# pc_afe4490_brk_v2.net
KiCad netlist of a schematic drawn in EAGLE
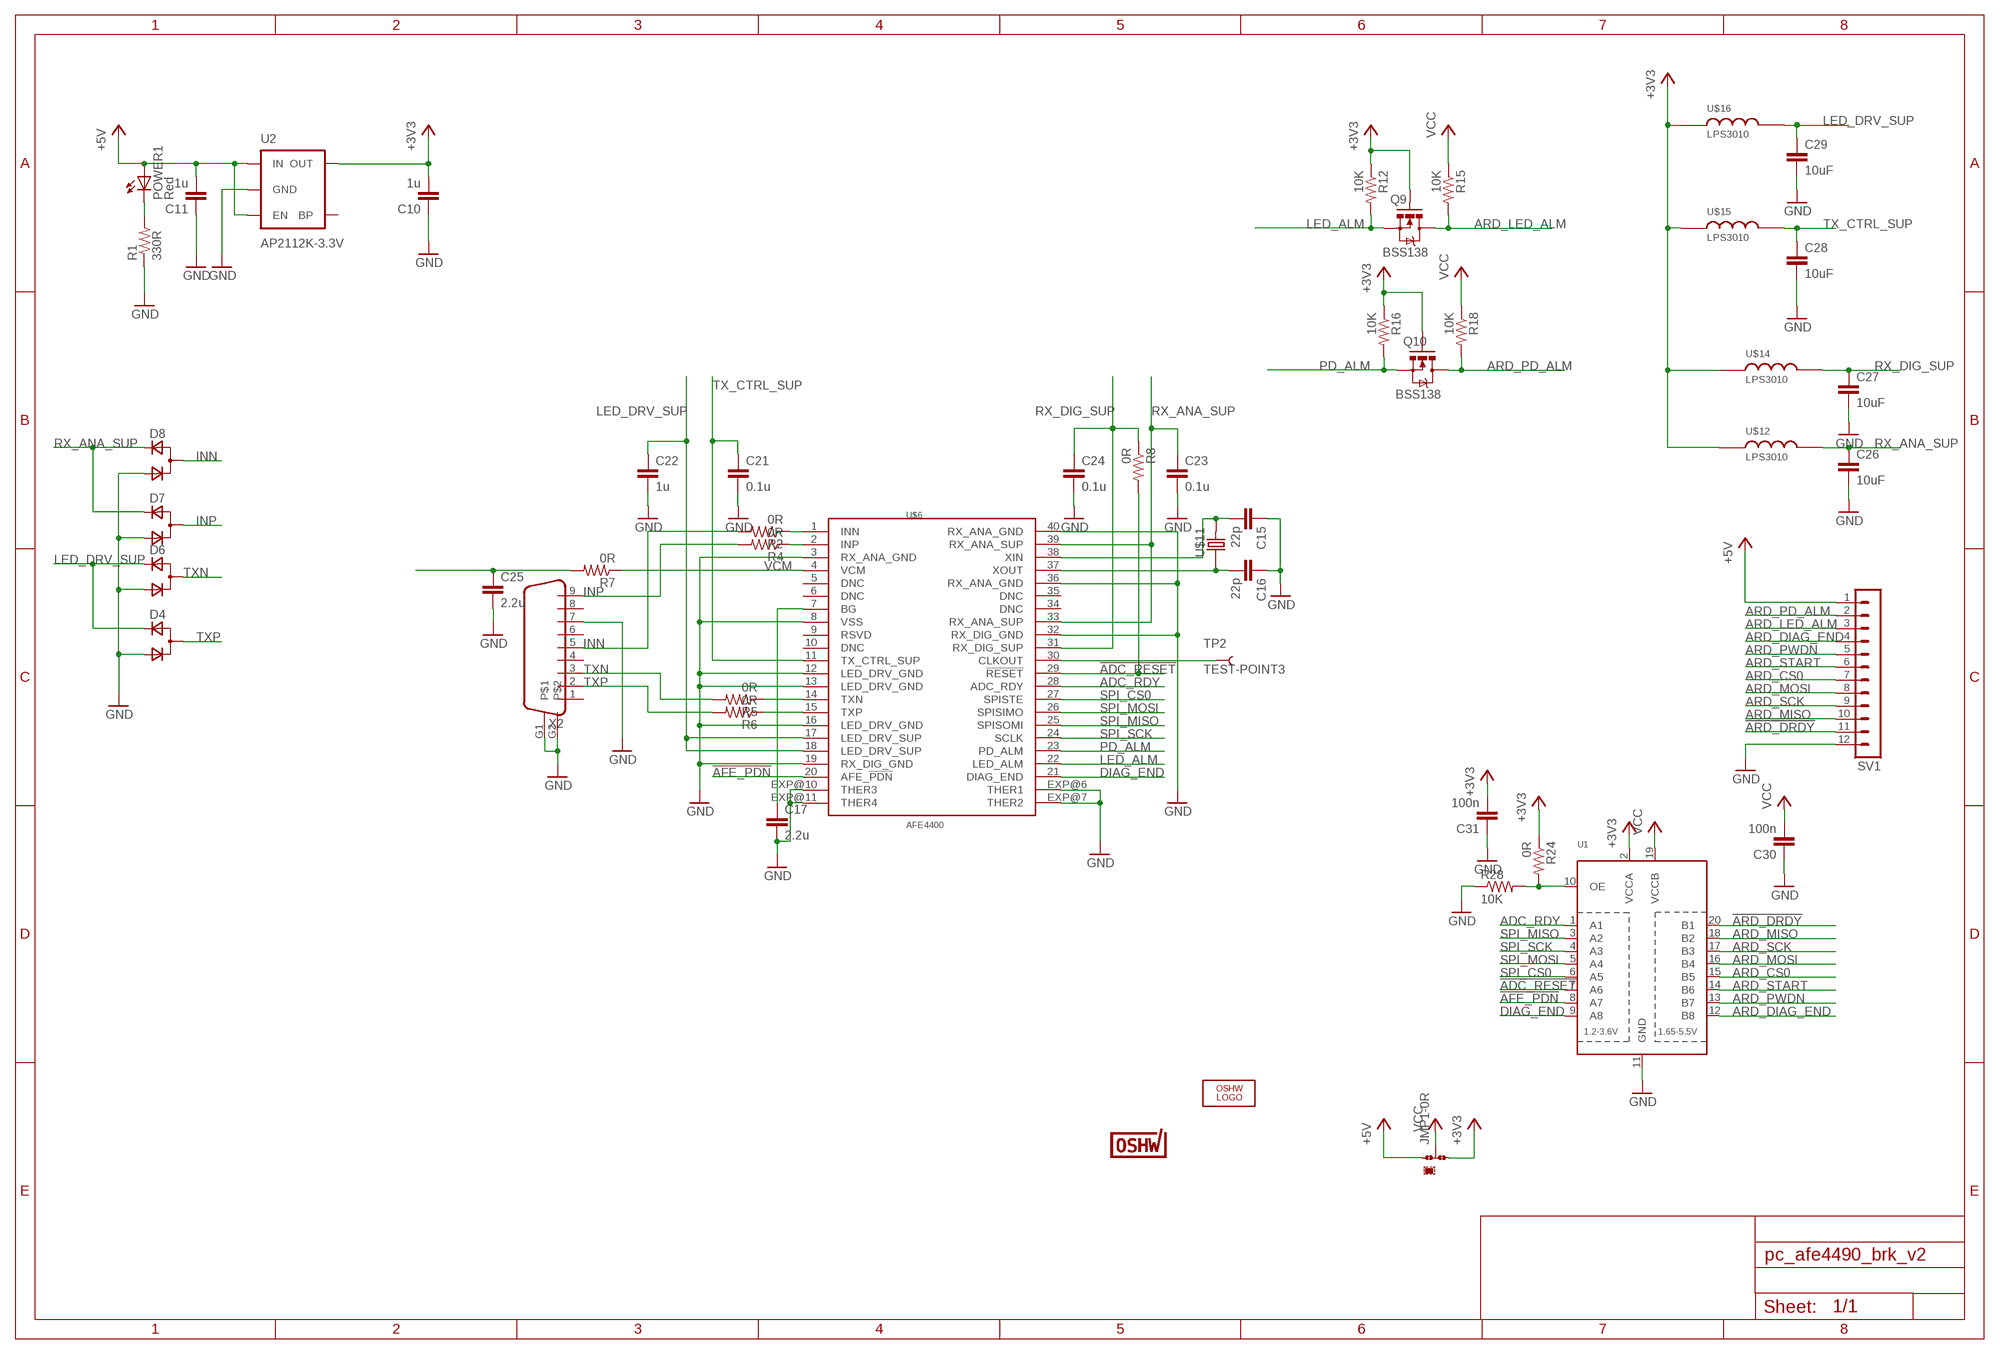
[diagram p0: schematic, sheet 1]

(export (version "E")
  (design (tool "Eeschema 10.0.6"))
  (components
    (comp (ref "C10")
      (value "1u")
      (footprint "eagle-import:C0805")
      (libsource (lib "eagle-import") (part "C-EUC0805"))
    )
    (comp (ref "C11")
      (value "1u")
      (footprint "eagle-import:C0805")
      (libsource (lib "eagle-import") (part "C-EUC0805"))
    )
    (comp (ref "C15")
      (value "22p")
      (footprint "eagle-import:C0402")
      (libsource (lib "eagle-import") (part "C-EUC0402"))
    )
    (comp (ref "C16")
      (value "22p")
      (footprint "eagle-import:C0402")
      (libsource (lib "eagle-import") (part "C-EUC0402"))
    )
    (comp (ref "C17")
      (value "2.2u")
      (footprint "eagle-import:C0402")
      (libsource (lib "eagle-import") (part "C-EUC0402"))
    )
    (comp (ref "C21")
      (value "0.1u")
      (footprint "eagle-import:C0805")
      (libsource (lib "eagle-import") (part "C-EUC0805"))
    )
    (comp (ref "C22")
      (value "1u")
      (footprint "eagle-import:C0805")
      (libsource (lib "eagle-import") (part "C-EUC0805"))
    )
    (comp (ref "C23")
      (value "0.1u")
      (footprint "eagle-import:C0805")
      (libsource (lib "eagle-import") (part "C-EUC0805"))
    )
    (comp (ref "C24")
      (value "0.1u")
      (footprint "eagle-import:C0805")
      (libsource (lib "eagle-import") (part "C-EUC0805"))
    )
    (comp (ref "C25")
      (value "2.2u")
      (footprint "eagle-import:C0402")
      (libsource (lib "eagle-import") (part "C-EUC0402"))
    )
    (comp (ref "C26")
      (value "10uF")
      (footprint "eagle-import:C0805")
      (libsource (lib "eagle-import") (part "C-EUC0805"))
    )
    (comp (ref "C27")
      (value "10uF")
      (footprint "eagle-import:C0805")
      (libsource (lib "eagle-import") (part "C-EUC0805"))
    )
    (comp (ref "C28")
      (value "10uF")
      (footprint "eagle-import:C0805")
      (libsource (lib "eagle-import") (part "C-EUC0805"))
    )
    (comp (ref "C29")
      (value "10uF")
      (footprint "eagle-import:C0805")
      (libsource (lib "eagle-import") (part "C-EUC0805"))
    )
    (comp (ref "C30")
      (value "100n")
      (footprint "eagle-import:C0402")
      (libsource (lib "eagle-import") (part "C-EUC0402"))
    )
    (comp (ref "C31")
      (value "100n")
      (footprint "eagle-import:C0402")
      (libsource (lib "eagle-import") (part "C-EUC0402"))
    )
    (comp (ref "D4")
      (value "D_ACACSOT323")
      (footprint "eagle-import:SOT323")
      (libsource (lib "eagle-import") (part "D_ACACSOT323"))
    )
    (comp (ref "D6")
      (value "D_ACACSOT323")
      (footprint "eagle-import:SOT323")
      (libsource (lib "eagle-import") (part "D_ACACSOT323"))
    )
    (comp (ref "D7")
      (value "D_ACACSOT323")
      (footprint "eagle-import:SOT323")
      (libsource (lib "eagle-import") (part "D_ACACSOT323"))
    )
    (comp (ref "D8")
      (value "D_ACACSOT323")
      (footprint "eagle-import:SOT323")
      (libsource (lib "eagle-import") (part "D_ACACSOT323"))
    )
    (comp (ref "JMP1")
      (value "0R-JUMPA")
      (footprint "eagle-import:A0R-JMP")
      (libsource (lib "eagle-import") (part "0R-JUMPA"))
    )
    (comp (ref "LOGO2")
      (value "OSHW_LOGO_FILLX0200-NT")
      (footprint "eagle-import:OSHW_FILLX200_NOTEXT")
      (libsource (lib "eagle-import") (part "OSHW_LOGO_FILLX0200-NT"))
    )
    (comp (ref "POWER1")
      (value "Red")
      (footprint "eagle-import:CHIPLED_0603")
      (libsource (lib "eagle-import") (part "LEDCHIPLED_0603"))
    )
    (comp (ref "Q9")
      (value "BSS138")
      (footprint "eagle-import:SOT23-3")
      (libsource (lib "eagle-import") (part "MOSFET-NCHANNELSMD"))
    )
    (comp (ref "Q10")
      (value "BSS138")
      (footprint "eagle-import:SOT23-3")
      (libsource (lib "eagle-import") (part "MOSFET-NCHANNELSMD"))
    )
    (comp (ref "R1")
      (value "330R")
      (footprint "eagle-import:R0805")
      (libsource (lib "eagle-import") (part "R-US_R0805"))
    )
    (comp (ref "R2")
      (value "0R")
      (footprint "eagle-import:R0402")
      (libsource (lib "eagle-import") (part "R-US_R0402"))
    )
    (comp (ref "R4")
      (value "0R")
      (footprint "eagle-import:R0402")
      (libsource (lib "eagle-import") (part "R-US_R0402"))
    )
    (comp (ref "R5")
      (value "0R")
      (footprint "eagle-import:R0805")
      (libsource (lib "eagle-import") (part "R-US_R0805"))
    )
    (comp (ref "R6")
      (value "0R")
      (footprint "eagle-import:R0805")
      (libsource (lib "eagle-import") (part "R-US_R0805"))
    )
    (comp (ref "R7")
      (value "0R")
      (footprint "eagle-import:R0402")
      (libsource (lib "eagle-import") (part "R-US_R0402"))
    )
    (comp (ref "R8")
      (value "0R")
      (footprint "eagle-import:R0805")
      (libsource (lib "eagle-import") (part "R-US_R0805"))
    )
    (comp (ref "R12")
      (value "10K")
      (footprint "eagle-import:0805")
      (libsource (lib "eagle-import") (part "RESISTOR0805-RES"))
    )
    (comp (ref "R15")
      (value "10K")
      (footprint "eagle-import:0805")
      (libsource (lib "eagle-import") (part "RESISTOR0805-RES"))
    )
    (comp (ref "R16")
      (value "10K")
      (footprint "eagle-import:0805")
      (libsource (lib "eagle-import") (part "RESISTOR0805-RES"))
    )
    (comp (ref "R18")
      (value "10K")
      (footprint "eagle-import:0805")
      (libsource (lib "eagle-import") (part "RESISTOR0805-RES"))
    )
    (comp (ref "R24")
      (value "0R")
      (footprint "eagle-import:0805")
      (libsource (lib "eagle-import") (part "RESISTOR0805-RES"))
    )
    (comp (ref "R28")
      (value "10K")
      (footprint "eagle-import:0805")
      (libsource (lib "eagle-import") (part "RESISTOR0805-RES"))
    )
    (comp (ref "SV1")
      (value "MA12-1")
      (footprint "eagle-import:MA12-1")
      (libsource (lib "eagle-import") (part "MA12-1"))
    )
    (comp (ref "TP2")
      (value "TEST-POINT3")
      (footprint "eagle-import:PAD.03X.03")
      (libsource (lib "eagle-import") (part "TEST-POINT3"))
    )
    (comp (ref "U$1")
      (value "PROTY-LOGO")
      (footprint "eagle-import:LOGO-PROTY")
      (libsource (lib "eagle-import") (part "PROTY-LOGO"))
    )
    (comp (ref "U$3")
      (value "PROTY_LOGO_WITH_TEXT")
      (footprint "eagle-import:PROTY_WITH_TEXT")
      (libsource (lib "eagle-import") (part "PROTY_LOGO_WITH_TEXT"))
    )
    (comp (ref "U$4")
      (value "CERT-SMALL")
      (footprint "eagle-import:CERT-SMALL-SILK")
      (libsource (lib "eagle-import") (part "CERT-SMALL"))
    )
    (comp (ref "U$6")
      (value "AFE4400")
      (footprint "eagle-import:QFN-40")
      (libsource (lib "eagle-import") (part "AFE4400"))
    )
    (comp (ref "U$11")
      (value "ABM3")
      (footprint "eagle-import:ABM3")
      (libsource (lib "eagle-import") (part "ABM3"))
    )
    (comp (ref "U$12")
      (value "LPS3010")
      (footprint "eagle-import:LPS")
      (libsource (lib "eagle-import") (part "LPS"))
    )
    (comp (ref "U$14")
      (value "LPS3010")
      (footprint "eagle-import:LPS")
      (libsource (lib "eagle-import") (part "LPS"))
    )
    (comp (ref "U$15")
      (value "LPS3010")
      (footprint "eagle-import:LPS")
      (libsource (lib "eagle-import") (part "LPS"))
    )
    (comp (ref "U$16")
      (value "LPS3010")
      (footprint "eagle-import:LPS")
      (libsource (lib "eagle-import") (part "LPS"))
    )
    (comp (ref "U1")
      (value "TXB0108PWR")
      (footprint "eagle-import:TSSOP20")
      (libsource (lib "eagle-import") (part "TXB0108PWR"))
    )
    (comp (ref "U2")
      (value "AP2112K-3.3V")
      (footprint "eagle-import:SOT23-5")
      (libsource (lib "eagle-import") (part "V_REG_LDOSMD"))
    )
    (comp (ref "X2")
      (value "DB9")
      (footprint "eagle-import:DB9")
      (libsource (lib "eagle-import") (part "DB9"))
    )
  )
  (nets
    (net (code "1") (name "+3V3") (class "Default")
      (node (ref "C10") (pin "2") (pinfunction "2_2") (pintype "passive"))
      (node (ref "C31") (pin "2") (pinfunction "2_2") (pintype "passive"))
      (node (ref "JMP1") (pin "3") (pinfunction "3_3") (pintype "passive"))
      (node (ref "Q10") (pin "1") (pinfunction "G_1") (pintype "passive"))
      (node (ref "Q9") (pin "1") (pinfunction "G_1") (pintype "passive"))
      (node (ref "R12") (pin "1") (pinfunction "1_1") (pintype "passive"))
      (node (ref "R16") (pin "1") (pinfunction "1_1") (pintype "passive"))
      (node (ref "R24") (pin "1") (pinfunction "1_1") (pintype "passive"))
      (node (ref "U$12") (pin "1") (pinfunction "P$1_1") (pintype "bidirectional"))
      (node (ref "U$14") (pin "1") (pinfunction "P$1_1") (pintype "bidirectional"))
      (node (ref "U$15") (pin "1") (pinfunction "P$1_1") (pintype "bidirectional"))
      (node (ref "U$16") (pin "1") (pinfunction "P$1_1") (pintype "bidirectional"))
      (node (ref "U1") (pin "2") (pinfunction "VCCA_2") (pintype "bidirectional"))
      (node (ref "U2") (pin "5") (pinfunction "OUT_5") (pintype "passive"))
    )
    (net (code "2") (name "+5V") (class "Default")
      (node (ref "C11") (pin "2") (pinfunction "2_2") (pintype "passive"))
      (node (ref "JMP1") (pin "1") (pinfunction "1_1") (pintype "passive"))
      (node (ref "POWER1") (pin "A") (pinfunction "A_A") (pintype "passive"))
      (node (ref "SV1") (pin "1") (pinfunction "1_1") (pintype "passive"))
      (node (ref "U2") (pin "1") (pinfunction "IN_1") (pintype "input"))
      (node (ref "U2") (pin "3") (pinfunction "EN_3") (pintype "input"))
    )
    (net (code "3") (name "/ADC_RDY") (class "Default")
      (node (ref "U$6") (pin "28") (pinfunction "ADC_RDY_28") (pintype "bidirectional"))
      (node (ref "U1") (pin "1") (pinfunction "A1_1") (pintype "bidirectional"))
    )
    (net (code "4") (name "/ARD_CS0") (class "Default")
      (node (ref "SV1") (pin "7") (pinfunction "7_7") (pintype "passive"))
      (node (ref "U1") (pin "15") (pinfunction "B5_15") (pintype "bidirectional"))
    )
    (net (code "5") (name "/ARD_DIAG_END") (class "Default")
      (node (ref "SV1") (pin "4") (pinfunction "4_4") (pintype "passive"))
      (node (ref "U1") (pin "12") (pinfunction "B8_12") (pintype "bidirectional"))
    )
    (net (code "6") (name "/ARD_LED_ALM") (class "Default")
      (node (ref "Q9") (pin "3") (pinfunction "D_3") (pintype "passive"))
      (node (ref "R15") (pin "2") (pinfunction "2_2") (pintype "passive"))
      (node (ref "SV1") (pin "3") (pinfunction "3_3") (pintype "passive"))
    )
    (net (code "7") (name "/ARD_MISO") (class "Default")
      (node (ref "SV1") (pin "10") (pinfunction "10_10") (pintype "passive"))
      (node (ref "U1") (pin "18") (pinfunction "B2_18") (pintype "bidirectional"))
    )
    (net (code "8") (name "/ARD_MOSI") (class "Default")
      (node (ref "SV1") (pin "8") (pinfunction "8_8") (pintype "passive"))
      (node (ref "U1") (pin "16") (pinfunction "B4_16") (pintype "bidirectional"))
    )
    (net (code "9") (name "/ARD_PD_ALM") (class "Default")
      (node (ref "Q10") (pin "3") (pinfunction "D_3") (pintype "passive"))
      (node (ref "R18") (pin "2") (pinfunction "2_2") (pintype "passive"))
      (node (ref "SV1") (pin "2") (pinfunction "2_2") (pintype "passive"))
    )
    (net (code "10") (name "/ARD_PWDN") (class "Default")
      (node (ref "SV1") (pin "5") (pinfunction "5_5") (pintype "passive"))
      (node (ref "U1") (pin "13") (pinfunction "B7_13") (pintype "bidirectional"))
    )
    (net (code "11") (name "/ARD_SCK") (class "Default")
      (node (ref "SV1") (pin "9") (pinfunction "9_9") (pintype "passive"))
      (node (ref "U1") (pin "17") (pinfunction "B3_17") (pintype "bidirectional"))
    )
    (net (code "12") (name "/ARD_START") (class "Default")
      (node (ref "SV1") (pin "6") (pinfunction "6_6") (pintype "passive"))
      (node (ref "U1") (pin "14") (pinfunction "B6_14") (pintype "bidirectional"))
    )
    (net (code "13") (name "/DIAG_END") (class "Default")
      (node (ref "U$6") (pin "21") (pinfunction "DIAG_END_21") (pintype "bidirectional"))
      (node (ref "U1") (pin "9") (pinfunction "A8_9") (pintype "bidirectional"))
    )
    (net (code "14") (name "/INN") (class "Default")
      (node (ref "D8") (pin "1") (pinfunction "CA_1") (pintype "passive"))
      (node (ref "R2") (pin "2") (pinfunction "2_2") (pintype "passive"))
      (node (ref "X2") (pin "5") (pinfunction "5_5") (pintype "passive"))
    )
    (net (code "15") (name "/INP") (class "Default")
      (node (ref "D7") (pin "1") (pinfunction "CA_1") (pintype "passive"))
      (node (ref "R4") (pin "2") (pinfunction "2_2") (pintype "passive"))
      (node (ref "X2") (pin "9") (pinfunction "9_9") (pintype "passive"))
    )
    (net (code "16") (name "/LED_ALM") (class "Default")
      (node (ref "Q9") (pin "2") (pinfunction "S_2") (pintype "passive"))
      (node (ref "R12") (pin "2") (pinfunction "2_2") (pintype "passive"))
      (node (ref "U$6") (pin "22") (pinfunction "LED_ALM_22") (pintype "bidirectional"))
    )
    (net (code "17") (name "/LED_DRV_SUP") (class "Default")
      (node (ref "C22") (pin "1") (pinfunction "1_1") (pintype "passive"))
      (node (ref "C29") (pin "1") (pinfunction "1_1") (pintype "passive"))
      (node (ref "D4") (pin "3") (pinfunction "A_3") (pintype "passive"))
      (node (ref "D6") (pin "3") (pinfunction "A_3") (pintype "passive"))
      (node (ref "U$16") (pin "2") (pinfunction "P$2_2") (pintype "bidirectional"))
      (node (ref "U$6") (pin "17") (pinfunction "LED_DRV_SUP_17") (pintype "bidirectional"))
      (node (ref "U$6") (pin "18") (pinfunction "LED_DRV_SUP_18") (pintype "bidirectional"))
    )
    (net (code "18") (name "/PD_ALM") (class "Default")
      (node (ref "Q10") (pin "2") (pinfunction "S_2") (pintype "passive"))
      (node (ref "R16") (pin "2") (pinfunction "2_2") (pintype "passive"))
      (node (ref "U$6") (pin "23") (pinfunction "PD_ALM_23") (pintype "bidirectional"))
    )
    (net (code "19") (name "/RX_ANA_SUP") (class "Default")
      (node (ref "C23") (pin "1") (pinfunction "1_1") (pintype "passive"))
      (node (ref "C26") (pin "1") (pinfunction "1_1") (pintype "passive"))
      (node (ref "D7") (pin "3") (pinfunction "A_3") (pintype "passive"))
      (node (ref "D8") (pin "3") (pinfunction "A_3") (pintype "passive"))
      (node (ref "U$12") (pin "2") (pinfunction "P$2_2") (pintype "bidirectional"))
      (node (ref "U$6") (pin "33") (pinfunction "RX_ANA_SUP_33") (pintype "bidirectional"))
      (node (ref "U$6") (pin "39") (pinfunction "RX_ANA_SUP_39") (pintype "bidirectional"))
    )
    (net (code "20") (name "/RX_DIG_SUP") (class "Default")
      (node (ref "C24") (pin "1") (pinfunction "1_1") (pintype "passive"))
      (node (ref "C27") (pin "1") (pinfunction "1_1") (pintype "passive"))
      (node (ref "R8") (pin "1") (pinfunction "1_1") (pintype "passive"))
      (node (ref "U$14") (pin "2") (pinfunction "P$2_2") (pintype "bidirectional"))
      (node (ref "U$6") (pin "31") (pinfunction "RX_DIG_SUP_31") (pintype "bidirectional"))
    )
    (net (code "21") (name "/SPI_CS0") (class "Default")
      (node (ref "U$6") (pin "27") (pinfunction "SPISTE_27") (pintype "bidirectional"))
      (node (ref "U1") (pin "6") (pinfunction "A5_6") (pintype "bidirectional"))
    )
    (net (code "22") (name "/SPI_MISO") (class "Default")
      (node (ref "U$6") (pin "25") (pinfunction "SPISOMI_25") (pintype "bidirectional"))
      (node (ref "U1") (pin "3") (pinfunction "A2_3") (pintype "bidirectional"))
    )
    (net (code "23") (name "/SPI_MOSI") (class "Default")
      (node (ref "U$6") (pin "26") (pinfunction "SPISIMO_26") (pintype "bidirectional"))
      (node (ref "U1") (pin "5") (pinfunction "A4_5") (pintype "bidirectional"))
    )
    (net (code "24") (name "/SPI_SCK") (class "Default")
      (node (ref "U$6") (pin "24") (pinfunction "SCLK_24") (pintype "bidirectional"))
      (node (ref "U1") (pin "4") (pinfunction "A3_4") (pintype "bidirectional"))
    )
    (net (code "25") (name "/TXN") (class "Default")
      (node (ref "D6") (pin "1") (pinfunction "CA_1") (pintype "passive"))
      (node (ref "R5") (pin "2") (pinfunction "2_2") (pintype "passive"))
      (node (ref "X2") (pin "3") (pinfunction "3_3") (pintype "passive"))
    )
    (net (code "26") (name "/TXP") (class "Default")
      (node (ref "D4") (pin "1") (pinfunction "CA_1") (pintype "passive"))
      (node (ref "R6") (pin "2") (pinfunction "2_2") (pintype "passive"))
      (node (ref "X2") (pin "2") (pinfunction "2_2") (pintype "passive"))
    )
    (net (code "27") (name "/TX_CTRL_SUP") (class "Default")
      (node (ref "C21") (pin "1") (pinfunction "1_1") (pintype "passive"))
      (node (ref "C28") (pin "1") (pinfunction "1_1") (pintype "passive"))
      (node (ref "U$15") (pin "2") (pinfunction "P$2_2") (pintype "bidirectional"))
      (node (ref "U$6") (pin "11") (pinfunction "TX_CTRL_SUP_11") (pintype "bidirectional"))
    )
    (net (code "28") (name "/VCM") (class "Default")
      (node (ref "R7") (pin "1") (pinfunction "1_1") (pintype "passive"))
      (node (ref "U$6") (pin "4") (pinfunction "VCM_4") (pintype "bidirectional"))
    )
    (net (code "29") (name "/~{ADC_RESET}") (class "Default")
      (node (ref "R8") (pin "2") (pinfunction "2_2") (pintype "passive"))
      (node (ref "U$6") (pin "29") (pinfunction "~{RESET}_29") (pintype "bidirectional"))
      (node (ref "U1") (pin "7") (pinfunction "A6_7") (pintype "bidirectional"))
    )
    (net (code "30") (name "/~{AFE_PDN}") (class "Default")
      (node (ref "U$6") (pin "20") (pinfunction "AFE_~{PDN}_20") (pintype "bidirectional"))
      (node (ref "U1") (pin "8") (pinfunction "A7_8") (pintype "bidirectional"))
    )
    (net (code "31") (name "/~{ARD_DRDY}") (class "Default")
      (node (ref "SV1") (pin "11") (pinfunction "11_11") (pintype "passive"))
      (node (ref "U1") (pin "20") (pinfunction "B1_20") (pintype "bidirectional"))
    )
    (net (code "32") (name "GND") (class "Default")
      (node (ref "C10") (pin "1") (pinfunction "1_1") (pintype "passive"))
      (node (ref "C11") (pin "1") (pinfunction "1_1") (pintype "passive"))
      (node (ref "C15") (pin "1") (pinfunction "1_1") (pintype "passive"))
      (node (ref "C16") (pin "1") (pinfunction "1_1") (pintype "passive"))
      (node (ref "C17") (pin "2") (pinfunction "2_2") (pintype "passive"))
      (node (ref "C21") (pin "2") (pinfunction "2_2") (pintype "passive"))
      (node (ref "C22") (pin "2") (pinfunction "2_2") (pintype "passive"))
      (node (ref "C23") (pin "2") (pinfunction "2_2") (pintype "passive"))
      (node (ref "C24") (pin "2") (pinfunction "2_2") (pintype "passive"))
      (node (ref "C25") (pin "2") (pinfunction "2_2") (pintype "passive"))
      (node (ref "C26") (pin "2") (pinfunction "2_2") (pintype "passive"))
      (node (ref "C27") (pin "2") (pinfunction "2_2") (pintype "passive"))
      (node (ref "C28") (pin "2") (pinfunction "2_2") (pintype "passive"))
      (node (ref "C29") (pin "2") (pinfunction "2_2") (pintype "passive"))
      (node (ref "C30") (pin "1") (pinfunction "1_1") (pintype "passive"))
      (node (ref "C31") (pin "1") (pinfunction "1_1") (pintype "passive"))
      (node (ref "D4") (pin "2") (pinfunction "C_2") (pintype "passive"))
      (node (ref "D6") (pin "2") (pinfunction "C_2") (pintype "passive"))
      (node (ref "D7") (pin "2") (pinfunction "C_2") (pintype "passive"))
      (node (ref "D8") (pin "2") (pinfunction "C_2") (pintype "passive"))
      (node (ref "R1") (pin "1") (pinfunction "1_1") (pintype "passive"))
      (node (ref "R28") (pin "1") (pinfunction "1_1") (pintype "passive"))
      (node (ref "SV1") (pin "12") (pinfunction "12_12") (pintype "passive"))
      (node (ref "U$6") (pin "12") (pinfunction "LED_DRV_GND_12") (pintype "bidirectional"))
      (node (ref "U$6") (pin "13") (pinfunction "LED_DRV_GND_13") (pintype "bidirectional"))
      (node (ref "U$6") (pin "16") (pinfunction "LED_DRV_GND_16") (pintype "bidirectional"))
      (node (ref "U$6") (pin "19") (pinfunction "RX_DIG_GND_19") (pintype "bidirectional"))
      (node (ref "U$6") (pin "3") (pinfunction "RX_ANA_GND_3") (pintype "bidirectional"))
      (node (ref "U$6") (pin "32") (pinfunction "RX_DIG_GND_32") (pintype "bidirectional"))
      (node (ref "U$6") (pin "36") (pinfunction "RX_ANA_GND_36") (pintype "bidirectional"))
      (node (ref "U$6") (pin "40") (pinfunction "RX_ANA_GND_40") (pintype "bidirectional"))
      (node (ref "U$6") (pin "8") (pinfunction "VSS_8") (pintype "bidirectional"))
      (node (ref "U$6") (pin "EXP@10") (pinfunction "THER3_EXP@10") (pintype "bidirectional"))
      (node (ref "U$6") (pin "EXP@11") (pinfunction "THER4_EXP@11") (pintype "bidirectional"))
      (node (ref "U$6") (pin "EXP@6") (pinfunction "THER1_EXP@6") (pintype "bidirectional"))
      (node (ref "U$6") (pin "EXP@7") (pinfunction "THER2_EXP@7") (pintype "bidirectional"))
      (node (ref "U1") (pin "11") (pinfunction "GND_11") (pintype "bidirectional"))
      (node (ref "U2") (pin "2") (pinfunction "GND_2") (pintype "input"))
      (node (ref "X2") (pin "7") (pinfunction "7_7") (pintype "passive"))
      (node (ref "X2") (pin "G1") (pinfunction "P$1_G1") (pintype "bidirectional"))
      (node (ref "X2") (pin "G2") (pinfunction "P$2_G2") (pintype "bidirectional"))
    )
    (net (code "33") (name "Net-(C25-Pad1)") (class "Default")
      (node (ref "C25") (pin "1") (pinfunction "1_1") (pintype "passive"))
      (node (ref "R7") (pin "2") (pinfunction "2_2") (pintype "passive"))
    )
    (net (code "34") (name "Net-(POWER1-PadC)") (class "Default")
      (node (ref "POWER1") (pin "C") (pinfunction "C_C") (pintype "passive"))
      (node (ref "R1") (pin "2") (pinfunction "2_2") (pintype "passive"))
    )
    (net (code "35") (name "Net-(TP2-1)") (class "Default")
      (node (ref "TP2") (pin "P$1") (pinfunction "1_P$1") (pintype "bidirectional"))
      (node (ref "U$6") (pin "30") (pinfunction "CLKOUT_30") (pintype "bidirectional"))
    )
    (net (code "36") (name "Net-(U$6-BG)") (class "Default")
      (node (ref "C17") (pin "1") (pinfunction "1_1") (pintype "passive"))
      (node (ref "U$6") (pin "7") (pinfunction "BG_7") (pintype "bidirectional"))
    )
    (net (code "37") (name "Net-(U$6-INN)") (class "Default")
      (node (ref "R2") (pin "1") (pinfunction "1_1") (pintype "passive"))
      (node (ref "U$6") (pin "1") (pinfunction "INN_1") (pintype "bidirectional"))
    )
    (net (code "38") (name "Net-(U$6-INP)") (class "Default")
      (node (ref "R4") (pin "1") (pinfunction "1_1") (pintype "passive"))
      (node (ref "U$6") (pin "2") (pinfunction "INP_2") (pintype "bidirectional"))
    )
    (net (code "39") (name "Net-(U$6-TXN)") (class "Default")
      (node (ref "R5") (pin "1") (pinfunction "1_1") (pintype "passive"))
      (node (ref "U$6") (pin "14") (pinfunction "TXN_14") (pintype "bidirectional"))
    )
    (net (code "40") (name "Net-(U$6-TXP)") (class "Default")
      (node (ref "R6") (pin "1") (pinfunction "1_1") (pintype "passive"))
      (node (ref "U$6") (pin "15") (pinfunction "TXP_15") (pintype "bidirectional"))
    )
    (net (code "41") (name "Net-(U$6-XIN)") (class "Default")
      (node (ref "C15") (pin "2") (pinfunction "2_2") (pintype "passive"))
      (node (ref "U$11") (pin "2") (pinfunction "2_2") (pintype "passive"))
      (node (ref "U$6") (pin "38") (pinfunction "XIN_38") (pintype "bidirectional"))
    )
    (net (code "42") (name "Net-(U$6-XOUT)") (class "Default")
      (node (ref "C16") (pin "2") (pinfunction "2_2") (pintype "passive"))
      (node (ref "U$11") (pin "1") (pinfunction "1_1") (pintype "passive"))
      (node (ref "U$6") (pin "37") (pinfunction "XOUT_37") (pintype "bidirectional"))
    )
    (net (code "43") (name "Net-(U1-OE)") (class "Default")
      (node (ref "R24") (pin "2") (pinfunction "2_2") (pintype "passive"))
      (node (ref "R28") (pin "2") (pinfunction "2_2") (pintype "passive"))
      (node (ref "U1") (pin "10") (pinfunction "OE_10") (pintype "bidirectional"))
    )
    (net (code "44") (name "VCC") (class "Default")
      (node (ref "C30") (pin "2") (pinfunction "2_2") (pintype "passive"))
      (node (ref "JMP1") (pin "2") (pinfunction "2_2") (pintype "passive"))
      (node (ref "R15") (pin "1") (pinfunction "1_1") (pintype "passive"))
      (node (ref "R18") (pin "1") (pinfunction "1_1") (pintype "passive"))
      (node (ref "U1") (pin "19") (pinfunction "VCCB_19") (pintype "bidirectional"))
    )
    (net (code "45") (name "unconnected-(U$6-DNC-Pad5)") (class "Default")
      (node (ref "U$6") (pin "5") (pinfunction "DNC_5") (pintype "bidirectional"))
    )
    (net (code "46") (name "unconnected-(U$6-DNC-Pad6)") (class "Default")
      (node (ref "U$6") (pin "6") (pinfunction "DNC_6") (pintype "bidirectional"))
    )
    (net (code "47") (name "unconnected-(U$6-DNC-Pad10)") (class "Default")
      (node (ref "U$6") (pin "10") (pinfunction "DNC_10") (pintype "bidirectional"))
    )
    (net (code "48") (name "unconnected-(U$6-DNC-Pad34)") (class "Default")
      (node (ref "U$6") (pin "34") (pinfunction "DNC_34") (pintype "bidirectional"))
    )
    (net (code "49") (name "unconnected-(U$6-DNC-Pad35)") (class "Default")
      (node (ref "U$6") (pin "35") (pinfunction "DNC_35") (pintype "bidirectional"))
    )
    (net (code "50") (name "unconnected-(U$6-RSVD-Pad9)") (class "Default")
      (node (ref "U$6") (pin "9") (pinfunction "RSVD_9") (pintype "bidirectional"))
    )
    (net (code "51") (name "unconnected-(U2-BP-Pad4)") (class "Default")
      (node (ref "U2") (pin "4") (pinfunction "BP_4") (pintype "input"))
    )
    (net (code "52") (name "unconnected-(X2-Pad1)") (class "Default")
      (node (ref "X2") (pin "1") (pinfunction "1_1") (pintype "passive"))
    )
    (net (code "53") (name "unconnected-(X2-Pad4)") (class "Default")
      (node (ref "X2") (pin "4") (pinfunction "4_4") (pintype "passive"))
    )
    (net (code "54") (name "unconnected-(X2-Pad6)") (class "Default")
      (node (ref "X2") (pin "6") (pinfunction "6_6") (pintype "passive"))
    )
    (net (code "55") (name "unconnected-(X2-Pad8)") (class "Default")
      (node (ref "X2") (pin "8") (pinfunction "8_8") (pintype "passive"))
    )
  )
)
